# scratchBotV2.net
KiCad netlist of a schematic drawn in EAGLE
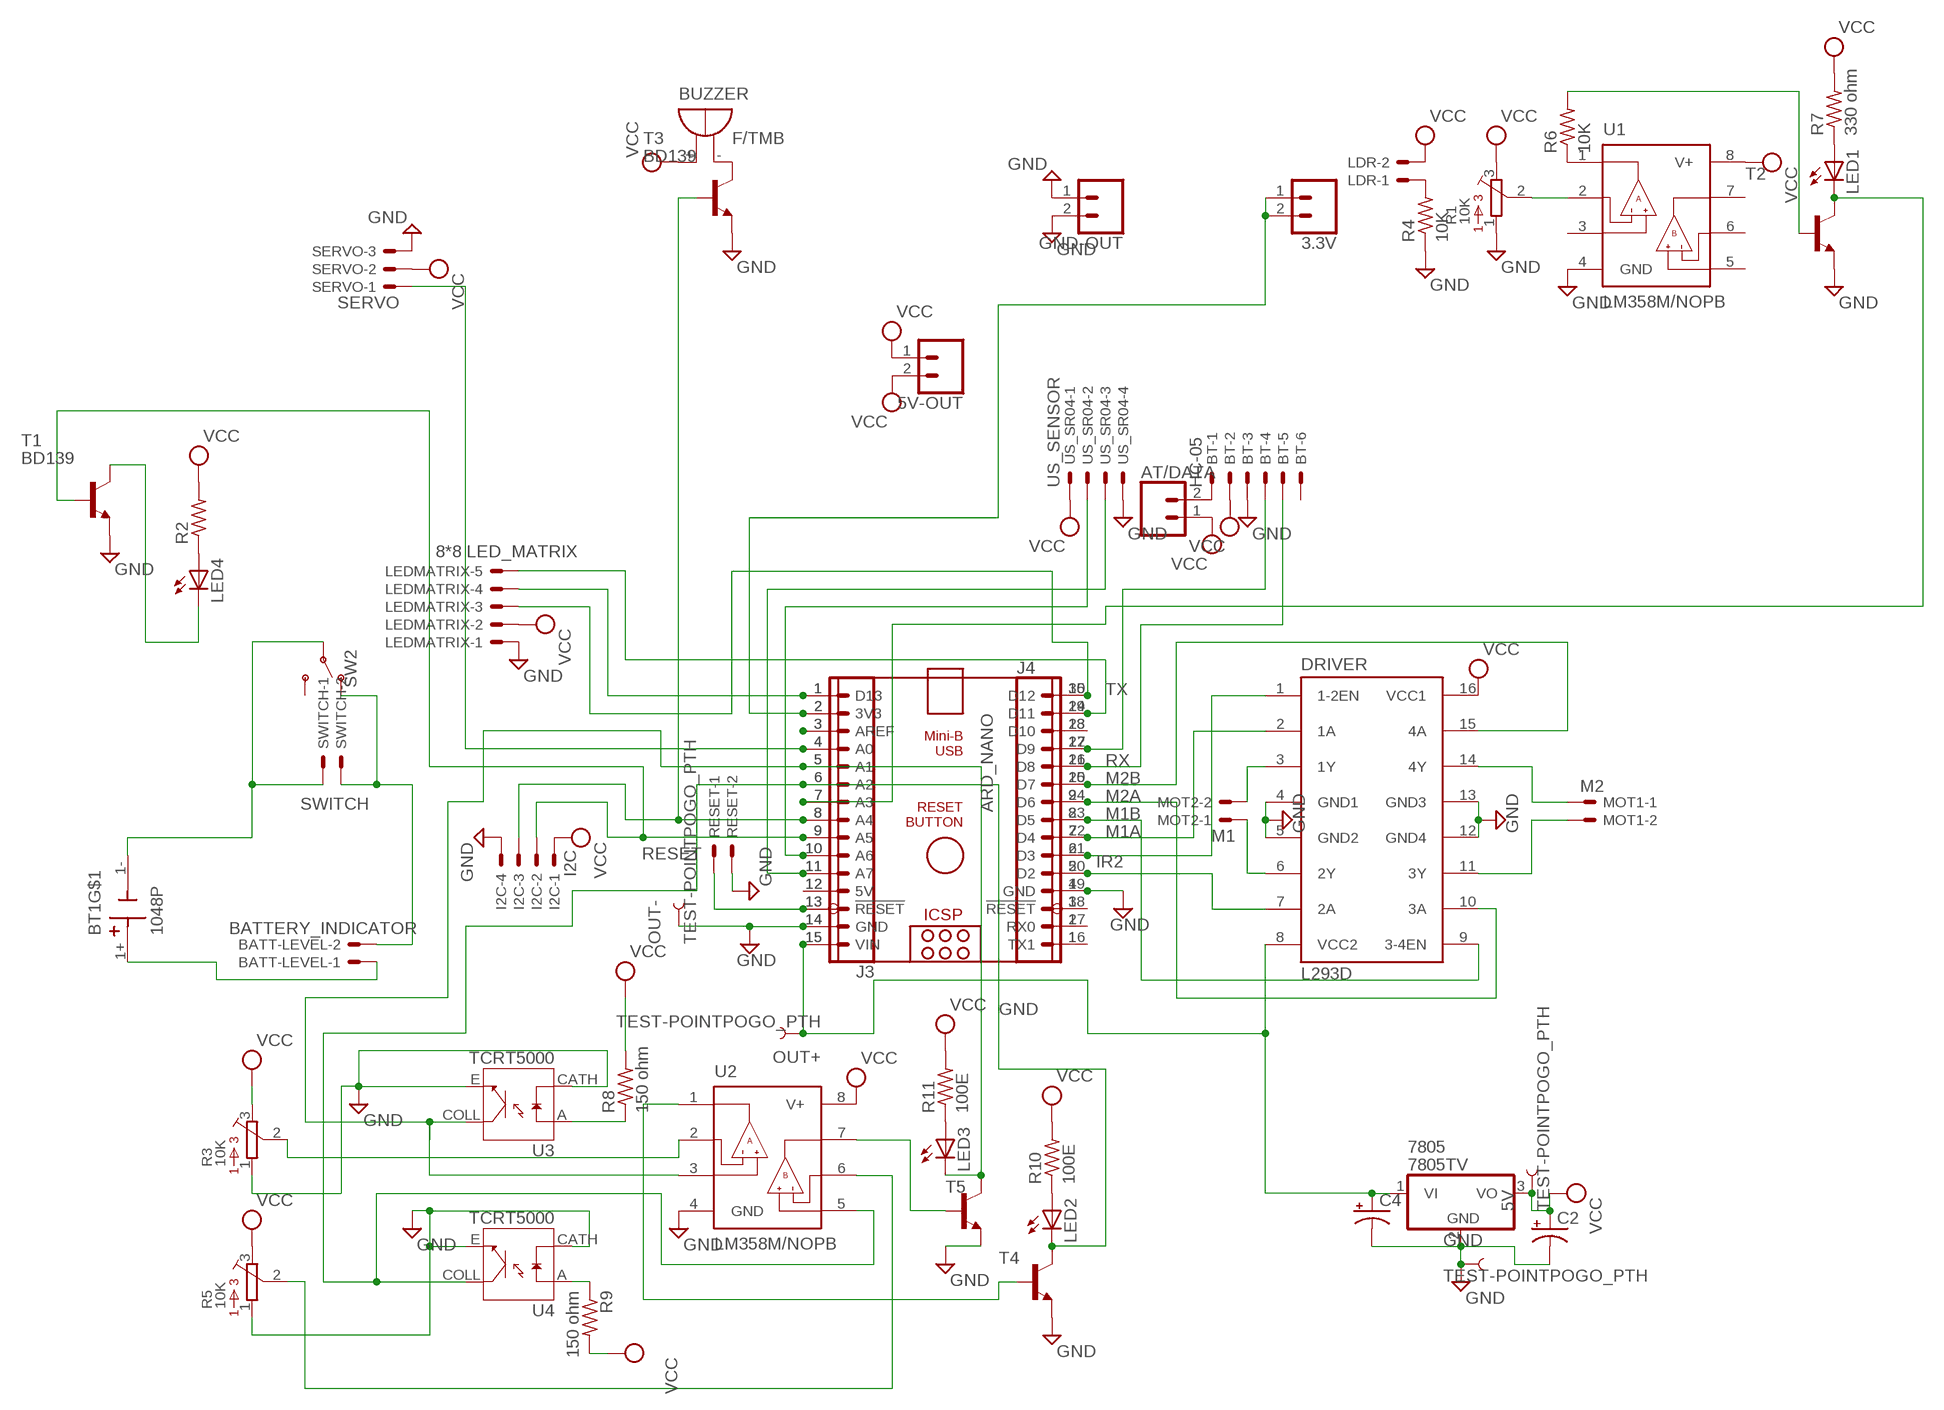
[diagram p0: schematic, sheet 1]

(export (version "E")
  (design (tool "Eeschema 10.0.6"))
  (components
    (comp (ref "3.3V")
      (value "CONN_02")
      (footprint "eagle-import:1X02")
      (libsource (lib "eagle-import") (part "CONN_02"))
    )
    (comp (ref "5V")
      (value "TEST-POINTPOGO_PTH")
      (footprint "eagle-import:1X01_NO_SILK")
      (libsource (lib "eagle-import") (part "TEST-POINTPOGO_PTH"))
    )
    (comp (ref "5V-OUT")
      (value "CONN_02")
      (footprint "eagle-import:1X02")
      (libsource (lib "eagle-import") (part "CONN_02"))
    )
    (comp (ref "7805")
      (value "7805TV")
      (footprint "eagle-import:TO220V")
      (libsource (lib "eagle-import") (part "78TV05"))
    )
    (comp (ref "ARD_NANO")
      (value "ARDUINO_NANO")
      (footprint "eagle-import:ARDUINO_NANO")
      (libsource (lib "eagle-import") (part "ARDUINO_NANO"))
    )
    (comp (ref "AT/DATA")
      (value "CONN_02")
      (footprint "eagle-import:1X02")
      (libsource (lib "eagle-import") (part "CONN_02"))
    )
    (comp (ref "BATT-LEVEL")
      (value "BATTERY_INDICATOR")
      (footprint "eagle-import:JST-XH-02-PACKAGE-LONG-PAD")
      (libsource (lib "eagle-import") (part "Rembrandt Electronics - JST XH Connectors v1-0 (1)_JST-XH-02-PIN-LONG-PAD"))
    )
    (comp (ref "BT")
      (value "HC-05")
      (footprint "eagle-import:JST-XH-06-PACKAGE-LONG-PAD")
      (libsource (lib "eagle-import") (part "JST-XH-06-PIN-LONG-PAD"))
    )
    (comp (ref "BT1")
      (value "1048P")
      (footprint "eagle-import:BAT_1048P")
      (fields (field (name "MF") "Keystone Electronics"))
      (libsource (lib "eagle-import") (part "1048P"))
    )
    (comp (ref "BUZZER")
      (value "F/TMB")
      (footprint "eagle-import:F_TMB")
      (libsource (lib "eagle-import") (part "F/TMB"))
    )
    (comp (ref "C2")
      (value "CPOL-USE2.5-5")
      (footprint "eagle-import:E2,5-5")
      (libsource (lib "eagle-import") (part "CPOL-USE2.5-5"))
    )
    (comp (ref "C4")
      (value "CPOL-USE2.5-5")
      (footprint "eagle-import:E2,5-5")
      (libsource (lib "eagle-import") (part "CPOL-USE2.5-5"))
    )
    (comp (ref "DRIVER")
      (value "L293D")
      (footprint "eagle-import:DIL16")
      (libsource (lib "eagle-import") (part "L293D"))
    )
    (comp (ref "GND")
      (value "TEST-POINTPOGO_PTH")
      (footprint "eagle-import:1X01_NO_SILK")
      (libsource (lib "eagle-import") (part "TEST-POINTPOGO_PTH"))
    )
    (comp (ref "GND-OUT")
      (value "CONN_02")
      (footprint "eagle-import:1X02")
      (libsource (lib "eagle-import") (part "CONN_02"))
    )
    (comp (ref "I2C")
      (value "I2C")
      (footprint "eagle-import:JST-XH-04-PACKAGE-LONG-PAD")
      (libsource (lib "eagle-import") (part "JST-XH-04-PIN-LONG-PAD"))
    )
    (comp (ref "J3")
      (value "CONN_15")
      (footprint "eagle-import:1X15")
      (libsource (lib "eagle-import") (part "CONN_15"))
    )
    (comp (ref "J4")
      (value "CONN_15")
      (footprint "eagle-import:1X15")
      (libsource (lib "eagle-import") (part "CONN_15"))
    )
    (comp (ref "LDR")
      (value "JST-XH-02-PIN-LONG-PAD")
      (footprint "eagle-import:JST-XH-02-PACKAGE-LONG-PAD")
      (libsource (lib "eagle-import") (part "JST-XH-02-PIN-LONG-PAD"))
    )
    (comp (ref "LED1")
      (value "LEDCHIPLED_1206")
      (footprint "eagle-import:CHIPLED_1206")
      (libsource (lib "eagle-import") (part "LEDCHIPLED_1206"))
    )
    (comp (ref "LED2")
      (value "LEDCHIPLED_1206")
      (footprint "eagle-import:CHIPLED_1206")
      (libsource (lib "eagle-import") (part "LEDCHIPLED_1206"))
    )
    (comp (ref "LED3")
      (value "LEDCHIPLED_1206")
      (footprint "eagle-import:CHIPLED_1206")
      (libsource (lib "eagle-import") (part "LEDCHIPLED_1206"))
    )
    (comp (ref "LED4")
      (value "LEDCHIPLED_1206")
      (footprint "eagle-import:CHIPLED_1206")
      (libsource (lib "eagle-import") (part "LEDCHIPLED_1206"))
    )
    (comp (ref "LEDMATRIX")
      (value "8*8 LED_MATRIX")
      (footprint "eagle-import:JST-XH-05-PACKAGE-LONG-PAD")
      (libsource (lib "eagle-import") (part "JST-XH-05-PIN-LONG-PAD"))
    )
    (comp (ref "MOT1")
      (value "M2")
      (footprint "eagle-import:JST-XH-02-PACKAGE-LONG-PAD")
      (libsource (lib "eagle-import") (part "Rembrandt Electronics - JST XH Connectors v1-0 (1)_JST-XH-02-PIN-LONG-PAD"))
    )
    (comp (ref "MOT2")
      (value "M1")
      (footprint "eagle-import:JST-XH-02-PACKAGE-LONG-PAD")
      (libsource (lib "eagle-import") (part "Rembrandt Electronics - JST XH Connectors v1-0 (1)_JST-XH-02-PIN-LONG-PAD"))
    )
    (comp (ref "OUT+")
      (value "TEST-POINTPOGO_PTH")
      (footprint "eagle-import:1X01_NO_SILK")
      (libsource (lib "eagle-import") (part "TEST-POINTPOGO_PTH"))
    )
    (comp (ref "OUT-")
      (value "TEST-POINTPOGO_PTH")
      (footprint "eagle-import:1X01_NO_SILK")
      (libsource (lib "eagle-import") (part "TEST-POINTPOGO_PTH"))
    )
    (comp (ref "R1")
      (value "10K")
      (footprint "eagle-import:3362H")
      (libsource (lib "eagle-import") (part "3362H"))
    )
    (comp (ref "R2")
      (value "R-US_0204/7")
      (footprint "eagle-import:0204_7")
      (libsource (lib "eagle-import") (part "R-US_0204/7"))
    )
    (comp (ref "R3")
      (value "10K")
      (footprint "eagle-import:3362H")
      (libsource (lib "eagle-import") (part "3362H"))
    )
    (comp (ref "R4")
      (value "10K")
      (footprint "eagle-import:M1206")
      (libsource (lib "eagle-import") (part "R-US_M1206"))
    )
    (comp (ref "R5")
      (value "10K")
      (footprint "eagle-import:3362H")
      (libsource (lib "eagle-import") (part "3362H"))
    )
    (comp (ref "R6")
      (value "10K")
      (footprint "eagle-import:M1206")
      (libsource (lib "eagle-import") (part "R-US_M1206"))
    )
    (comp (ref "R7")
      (value "330 ohm")
      (footprint "eagle-import:M1206")
      (libsource (lib "eagle-import") (part "R-US_M1206"))
    )
    (comp (ref "R8")
      (value "150 ohm")
      (footprint "eagle-import:M1206")
      (libsource (lib "eagle-import") (part "R-US_M1206"))
    )
    (comp (ref "R9")
      (value "150 ohm")
      (footprint "eagle-import:M1206")
      (libsource (lib "eagle-import") (part "R-US_M1206"))
    )
    (comp (ref "R10")
      (value "100E")
      (footprint "eagle-import:M1206")
      (libsource (lib "eagle-import") (part "R-US_M1206"))
    )
    (comp (ref "R11")
      (value "100E")
      (footprint "eagle-import:M1206")
      (libsource (lib "eagle-import") (part "R-US_M1206"))
    )
    (comp (ref "RESET")
      (value "RESET")
      (footprint "eagle-import:JST-XH-02-PACKAGE-LONG-PAD")
      (libsource (lib "eagle-import") (part "Rembrandt Electronics - JST XH Connectors v1-0 (1)_JST-XH-02-PIN-LONG-PAD"))
    )
    (comp (ref "SERVO")
      (value "SERVO")
      (footprint "eagle-import:JST-XH-03-PACKAGE-LONG-PAD")
      (libsource (lib "eagle-import") (part "JST-XH-03-PIN-LONG-PAD"))
    )
    (comp (ref "SW2")
      (value "SWITCH-SPDT-PTH-11.6X4.0MM")
      (footprint "eagle-import:SWITCH_SPDT_PTH_11.6X4.0MM")
      (libsource (lib "eagle-import") (part "SWITCH-SPDT-PTH-11.6X4.0MM"))
    )
    (comp (ref "SWITCH")
      (value "SWITCH")
      (footprint "eagle-import:JST-XH-02-PACKAGE-LONG-PAD")
      (libsource (lib "eagle-import") (part "Rembrandt Electronics - JST XH Connectors v1-0 (1)_JST-XH-02-PIN-LONG-PAD"))
    )
    (comp (ref "T1")
      (value "BD139")
      (footprint "eagle-import:TO126")
      (libsource (lib "eagle-import") (part "BD139"))
    )
    (comp (ref "T2")
      (value "-NPN-SOT23-EBC")
      (footprint "eagle-import:SOT23-EBC")
      (libsource (lib "eagle-import") (part "-NPN-SOT23-EBC"))
    )
    (comp (ref "T3")
      (value "BD139")
      (footprint "eagle-import:TO126")
      (libsource (lib "eagle-import") (part "BD139"))
    )
    (comp (ref "T4")
      (value "-NPN-SOT23-EBC")
      (footprint "eagle-import:SOT23-EBC")
      (libsource (lib "eagle-import") (part "-NPN-SOT23-EBC"))
    )
    (comp (ref "T5")
      (value "-NPN-SOT23-EBC")
      (footprint "eagle-import:SOT23-EBC")
      (libsource (lib "eagle-import") (part "-NPN-SOT23-EBC"))
    )
    (comp (ref "U1")
      (value "LM358M/NOPB")
      (footprint "eagle-import:SOIC127P599X175-8N")
      (fields (field (name "MF") "Texas Instruments"))
      (libsource (lib "eagle-import") (part "LM358M/NOPB"))
    )
    (comp (ref "U2")
      (value "LM358M/NOPB")
      (footprint "eagle-import:SOIC127P599X175-8N")
      (fields (field (name "MF") "Texas Instruments"))
      (libsource (lib "eagle-import") (part "LM358M/NOPB"))
    )
    (comp (ref "U3")
      (value "TCRT5000")
      (footprint "eagle-import:OPTO_TCRT5000")
      (fields (field (name "MF") "Vishay"))
      (libsource (lib "eagle-import") (part "TCRT5000"))
    )
    (comp (ref "U4")
      (value "TCRT5000")
      (footprint "eagle-import:OPTO_TCRT5000")
      (fields (field (name "MF") "Vishay"))
      (libsource (lib "eagle-import") (part "TCRT5000"))
    )
    (comp (ref "US_SR04")
      (value "US_SENSOR")
      (footprint "eagle-import:JST-XH-04-PACKAGE-LONG-PAD")
      (libsource (lib "eagle-import") (part "JST-XH-04-PIN-LONG-PAD"))
    )
  )
  (nets
    (net (code "1") (name "/IR2") (class "Default")
      (node (ref "ARD_NANO") (pin "21") (pinfunction "D3_21") (pintype "bidirectional"))
      (node (ref "DRIVER") (pin "1") (pinfunction "1-2EN_1") (pintype "input"))
      (node (ref "J4") (pin "6") (pinfunction "6_6") (pintype "passive"))
    )
    (net (code "2") (name "/M1A") (class "Default")
      (node (ref "ARD_NANO") (pin "22") (pinfunction "D4_22") (pintype "bidirectional"))
      (node (ref "DRIVER") (pin "2") (pinfunction "1A_2") (pintype "input"))
      (node (ref "J4") (pin "7") (pinfunction "7_7") (pintype "passive"))
    )
    (net (code "3") (name "/M1B") (class "Default")
      (node (ref "ARD_NANO") (pin "23") (pinfunction "D5_23") (pintype "bidirectional"))
      (node (ref "DRIVER") (pin "9") (pinfunction "3-4EN_9") (pintype "input"))
      (node (ref "J4") (pin "8") (pinfunction "8_8") (pintype "passive"))
    )
    (net (code "4") (name "/M2A") (class "Default")
      (node (ref "ARD_NANO") (pin "24") (pinfunction "D6_24") (pintype "bidirectional"))
      (node (ref "DRIVER") (pin "10") (pinfunction "3A_10") (pintype "input"))
      (node (ref "J4") (pin "9") (pinfunction "9_9") (pintype "passive"))
    )
    (net (code "5") (name "/M2B") (class "Default")
      (node (ref "ARD_NANO") (pin "25") (pinfunction "D7_25") (pintype "bidirectional"))
      (node (ref "DRIVER") (pin "15") (pinfunction "4A_15") (pintype "input"))
      (node (ref "J4") (pin "10") (pinfunction "10_10") (pintype "passive"))
    )
    (net (code "6") (name "/RX") (class "Default")
      (node (ref "ARD_NANO") (pin "26") (pinfunction "D8_26") (pintype "bidirectional"))
      (node (ref "BT") (pin "5") (pinfunction "S_5") (pintype "passive"))
      (node (ref "J4") (pin "11") (pinfunction "11_11") (pintype "passive"))
    )
    (net (code "7") (name "/TX") (class "Default")
      (node (ref "ARD_NANO") (pin "30") (pinfunction "D12_30") (pintype "bidirectional"))
      (node (ref "J4") (pin "15") (pinfunction "15_15") (pintype "passive"))
      (node (ref "LEDMATRIX") (pin "3") (pinfunction "S_3") (pintype "passive"))
    )
    (net (code "8") (name "GND") (class "Default")
      (node (ref "7805") (pin "2") (pinfunction "GND_2") (pintype "passive"))
      (node (ref "ARD_NANO") (pin "14") (pinfunction "GND_14") (pintype "power_in"))
      (node (ref "ARD_NANO") (pin "19") (pinfunction "GND_19") (pintype "power_in"))
      (node (ref "BT") (pin "3") (pinfunction "S_3") (pintype "passive"))
      (node (ref "C2") (pin "-") (pinfunction "-_-") (pintype "passive"))
      (node (ref "C4") (pin "-") (pinfunction "-_-") (pintype "passive"))
      (node (ref "DRIVER") (pin "12") (pinfunction "GND4_12") (pintype "power_in"))
      (node (ref "DRIVER") (pin "13") (pinfunction "GND3_13") (pintype "power_in"))
      (node (ref "DRIVER") (pin "4") (pinfunction "GND1_4") (pintype "power_in"))
      (node (ref "DRIVER") (pin "5") (pinfunction "GND2_5") (pintype "power_in"))
      (node (ref "GND") (pin "1") (pinfunction "1_1") (pintype "bidirectional"))
      (node (ref "GND-OUT") (pin "1") (pinfunction "1_1") (pintype "passive"))
      (node (ref "GND-OUT") (pin "2") (pinfunction "2_2") (pintype "passive"))
      (node (ref "I2C") (pin "4") (pinfunction "S_4") (pintype "passive"))
      (node (ref "J3") (pin "14") (pinfunction "14_14") (pintype "passive"))
      (node (ref "J4") (pin "4") (pinfunction "4_4") (pintype "passive"))
      (node (ref "LEDMATRIX") (pin "1") (pinfunction "S_1") (pintype "passive"))
      (node (ref "OUT-") (pin "1") (pinfunction "1_1") (pintype "bidirectional"))
      (node (ref "R1") (pin "1") (pinfunction "1_1") (pintype "passive"))
      (node (ref "R3") (pin "1") (pinfunction "1_1") (pintype "passive"))
      (node (ref "R4") (pin "1") (pinfunction "1_1") (pintype "passive"))
      (node (ref "R5") (pin "1") (pinfunction "1_1") (pintype "passive"))
      (node (ref "RESET") (pin "2") (pinfunction "S_2") (pintype "passive"))
      (node (ref "SERVO") (pin "3") (pinfunction "S_3") (pintype "passive"))
      (node (ref "T1") (pin "1") (pinfunction "E_1") (pintype "passive"))
      (node (ref "T2") (pin "E") (pinfunction "E_E") (pintype "passive"))
      (node (ref "T3") (pin "1") (pinfunction "E_1") (pintype "passive"))
      (node (ref "T4") (pin "E") (pinfunction "E_E") (pintype "passive"))
      (node (ref "T5") (pin "E") (pinfunction "E_E") (pintype "passive"))
      (node (ref "U1") (pin "4") (pinfunction "GND_4") (pintype "power_in"))
      (node (ref "U2") (pin "4") (pinfunction "GND_4") (pintype "power_in"))
      (node (ref "U3") (pin "CATH") (pinfunction "CATH_CATH") (pintype "passive"))
      (node (ref "U3") (pin "E") (pinfunction "E_E") (pintype "passive"))
      (node (ref "U4") (pin "CATH") (pinfunction "CATH_CATH") (pintype "passive"))
      (node (ref "U4") (pin "E") (pinfunction "E_E") (pintype "passive"))
      (node (ref "US_SR04") (pin "4") (pinfunction "S_4") (pintype "passive"))
    )
    (net (code "9") (name "Net-(7805-VI)") (class "Default")
      (node (ref "7805") (pin "1") (pinfunction "VI_1") (pintype "input"))
      (node (ref "ARD_NANO") (pin "15") (pinfunction "VIN_15") (pintype "power_in"))
      (node (ref "C4") (pin "+") (pinfunction "+_+") (pintype "passive"))
      (node (ref "DRIVER") (pin "8") (pinfunction "VCC2_8") (pintype "power_in"))
      (node (ref "J3") (pin "15") (pinfunction "15_15") (pintype "passive"))
      (node (ref "OUT+") (pin "1") (pinfunction "1_1") (pintype "bidirectional"))
    )
    (net (code "10") (name "Net-(ARD_NANO-3V3)") (class "Default")
      (node (ref "3.3V") (pin "1") (pinfunction "1_1") (pintype "passive"))
      (node (ref "3.3V") (pin "2") (pinfunction "2_2") (pintype "passive"))
      (node (ref "ARD_NANO") (pin "2") (pinfunction "3V3_2") (pintype "output"))
      (node (ref "J3") (pin "2") (pinfunction "2_2") (pintype "passive"))
    )
    (net (code "11") (name "Net-(ARD_NANO-5V)") (class "Default")
      (node (ref "ARD_NANO") (pin "12") (pinfunction "5V_12") (pintype "power_in"))
      (node (ref "J3") (pin "12") (pinfunction "12_12") (pintype "passive"))
    )
    (net (code "12") (name "Net-(ARD_NANO-A0)") (class "Default")
      (node (ref "ARD_NANO") (pin "4") (pinfunction "A0_4") (pintype "bidirectional"))
      (node (ref "J3") (pin "4") (pinfunction "4_4") (pintype "passive"))
      (node (ref "SERVO") (pin "1") (pinfunction "S_1") (pintype "passive"))
    )
    (net (code "13") (name "Net-(ARD_NANO-A1)") (class "Default")
      (node (ref "ARD_NANO") (pin "5") (pinfunction "A1_5") (pintype "bidirectional"))
      (node (ref "J3") (pin "5") (pinfunction "5_5") (pintype "passive"))
      (node (ref "LED3") (pin "C") (pinfunction "C_C") (pintype "passive"))
      (node (ref "T5") (pin "C") (pinfunction "C_C") (pintype "passive"))
      (node (ref "U2") (pin "3") (pinfunction "+INA_3") (pintype "input"))
      (node (ref "U3") (pin "COLL") (pinfunction "COLL_COLL") (pintype "passive"))
    )
    (net (code "14") (name "Net-(ARD_NANO-A2)") (class "Default")
      (node (ref "ARD_NANO") (pin "6") (pinfunction "A2_6") (pintype "bidirectional"))
      (node (ref "J3") (pin "6") (pinfunction "6_6") (pintype "passive"))
      (node (ref "LED2") (pin "C") (pinfunction "C_C") (pintype "passive"))
      (node (ref "T4") (pin "C") (pinfunction "C_C") (pintype "passive"))
      (node (ref "U2") (pin "5") (pinfunction "+INB_5") (pintype "input"))
      (node (ref "U4") (pin "COLL") (pinfunction "COLL_COLL") (pintype "passive"))
    )
    (net (code "15") (name "Net-(ARD_NANO-A3)") (class "Default")
      (node (ref "ARD_NANO") (pin "7") (pinfunction "A3_7") (pintype "bidirectional"))
      (node (ref "J3") (pin "7") (pinfunction "7_7") (pintype "passive"))
      (node (ref "LED1") (pin "C") (pinfunction "C_C") (pintype "passive"))
      (node (ref "T2") (pin "C") (pinfunction "C_C") (pintype "passive"))
    )
    (net (code "16") (name "Net-(ARD_NANO-A4)") (class "Default")
      (node (ref "ARD_NANO") (pin "8") (pinfunction "A4_8") (pintype "bidirectional"))
      (node (ref "I2C") (pin "3") (pinfunction "S_3") (pintype "passive"))
      (node (ref "J3") (pin "8") (pinfunction "8_8") (pintype "passive"))
      (node (ref "T3") (pin "3") (pinfunction "B_3") (pintype "passive"))
    )
    (net (code "17") (name "Net-(ARD_NANO-A5)") (class "Default")
      (node (ref "ARD_NANO") (pin "9") (pinfunction "A5_9") (pintype "bidirectional"))
      (node (ref "I2C") (pin "2") (pinfunction "S_2") (pintype "passive"))
      (node (ref "J3") (pin "9") (pinfunction "9_9") (pintype "passive"))
      (node (ref "T1") (pin "3") (pinfunction "B_3") (pintype "passive"))
    )
    (net (code "18") (name "Net-(ARD_NANO-A6)") (class "Default")
      (node (ref "ARD_NANO") (pin "10") (pinfunction "A6_10") (pintype "bidirectional"))
      (node (ref "J3") (pin "10") (pinfunction "10_10") (pintype "passive"))
      (node (ref "US_SR04") (pin "2") (pinfunction "S_2") (pintype "passive"))
    )
    (net (code "19") (name "Net-(ARD_NANO-A7)") (class "Default")
      (node (ref "ARD_NANO") (pin "11") (pinfunction "A7_11") (pintype "bidirectional"))
      (node (ref "J3") (pin "11") (pinfunction "11_11") (pintype "passive"))
      (node (ref "US_SR04") (pin "3") (pinfunction "S_3") (pintype "passive"))
    )
    (net (code "20") (name "Net-(ARD_NANO-AREF)") (class "Default")
      (node (ref "ARD_NANO") (pin "3") (pinfunction "AREF_3") (pintype "input"))
      (node (ref "J3") (pin "3") (pinfunction "3_3") (pintype "passive"))
    )
    (net (code "21") (name "Net-(ARD_NANO-D2)") (class "Default")
      (node (ref "ARD_NANO") (pin "20") (pinfunction "D2_20") (pintype "bidirectional"))
      (node (ref "DRIVER") (pin "7") (pinfunction "2A_7") (pintype "input"))
      (node (ref "J4") (pin "5") (pinfunction "5_5") (pintype "passive"))
    )
    (net (code "22") (name "Net-(ARD_NANO-D9)") (class "Default")
      (node (ref "ARD_NANO") (pin "27") (pinfunction "D9_27") (pintype "bidirectional"))
      (node (ref "BT") (pin "4") (pinfunction "S_4") (pintype "passive"))
      (node (ref "J4") (pin "12") (pinfunction "12_12") (pintype "passive"))
    )
    (net (code "23") (name "Net-(ARD_NANO-D10)") (class "Default")
      (node (ref "ARD_NANO") (pin "28") (pinfunction "D10_28") (pintype "bidirectional"))
      (node (ref "J4") (pin "13") (pinfunction "13_13") (pintype "passive"))
    )
    (net (code "24") (name "Net-(ARD_NANO-D11)") (class "Default")
      (node (ref "ARD_NANO") (pin "29") (pinfunction "D11_29") (pintype "bidirectional"))
      (node (ref "J4") (pin "14") (pinfunction "14_14") (pintype "passive"))
      (node (ref "LEDMATRIX") (pin "5") (pinfunction "S_5") (pintype "passive"))
    )
    (net (code "25") (name "Net-(ARD_NANO-D13)") (class "Default")
      (node (ref "ARD_NANO") (pin "1") (pinfunction "D13_1") (pintype "bidirectional"))
      (node (ref "J3") (pin "1") (pinfunction "1_1") (pintype "passive"))
      (node (ref "LEDMATRIX") (pin "4") (pinfunction "S_4") (pintype "passive"))
    )
    (net (code "26") (name "Net-(ARD_NANO-RX0)") (class "Default")
      (node (ref "ARD_NANO") (pin "17") (pinfunction "RX0_17") (pintype "bidirectional"))
      (node (ref "J4") (pin "2") (pinfunction "2_2") (pintype "passive"))
    )
    (net (code "27") (name "Net-(ARD_NANO-TX1)") (class "Default")
      (node (ref "ARD_NANO") (pin "16") (pinfunction "TX1_16") (pintype "bidirectional"))
      (node (ref "J4") (pin "1") (pinfunction "1_1") (pintype "passive"))
    )
    (net (code "28") (name "Net-(ARD_NANO-~{RESET}-Pad18)") (class "Default")
      (node (ref "ARD_NANO") (pin "18") (pinfunction "~{RESET}_18") (pintype "input"))
      (node (ref "J4") (pin "3") (pinfunction "3_3") (pintype "passive"))
    )
    (net (code "29") (name "Net-(BATT-LEVELA-S)") (class "Default")
      (node (ref "BATT-LEVEL") (pin "1") (pinfunction "S_1") (pintype "passive"))
      (node (ref "BT1") (pin "1+") (pinfunction "1+_1+") (pintype "passive"))
    )
    (net (code "30") (name "Net-(BATT-LEVELB-S)") (class "Default")
      (node (ref "BATT-LEVEL") (pin "2") (pinfunction "S_2") (pintype "passive"))
      (node (ref "SW2") (pin "1") (pinfunction "O_1") (pintype "passive"))
      (node (ref "SWITCH") (pin "2") (pinfunction "S_2") (pintype "passive"))
    )
    (net (code "31") (name "Net-(BTA-S)") (class "Default")
      (node (ref "AT/DATA") (pin "2") (pinfunction "2_2") (pintype "passive"))
      (node (ref "BT") (pin "1") (pinfunction "S_1") (pintype "passive"))
    )
    (net (code "32") (name "Net-(DRIVER-1Y)") (class "Default")
      (node (ref "DRIVER") (pin "3") (pinfunction "1Y_3") (pintype "output"))
      (node (ref "MOT2") (pin "2") (pinfunction "S_2") (pintype "passive"))
    )
    (net (code "33") (name "Net-(DRIVER-2Y)") (class "Default")
      (node (ref "DRIVER") (pin "6") (pinfunction "2Y_6") (pintype "output"))
      (node (ref "MOT2") (pin "1") (pinfunction "S_1") (pintype "passive"))
    )
    (net (code "34") (name "Net-(DRIVER-3Y)") (class "Default")
      (node (ref "DRIVER") (pin "11") (pinfunction "3Y_11") (pintype "output"))
      (node (ref "MOT1") (pin "2") (pinfunction "S_2") (pintype "passive"))
    )
    (net (code "35") (name "Net-(DRIVER-4Y)") (class "Default")
      (node (ref "DRIVER") (pin "14") (pinfunction "4Y_14") (pintype "output"))
      (node (ref "MOT1") (pin "1") (pinfunction "S_1") (pintype "passive"))
    )
    (net (code "36") (name "Net-(LDRA-S)") (class "Default")
      (node (ref "LDR") (pin "1") (pinfunction "S_1") (pintype "passive"))
      (node (ref "R4") (pin "2") (pinfunction "2_2") (pintype "passive"))
    )
    (net (code "37") (name "Net-(LED1-PadA)") (class "Default")
      (node (ref "LED1") (pin "A") (pinfunction "A_A") (pintype "passive"))
      (node (ref "R7") (pin "1") (pinfunction "1_1") (pintype "passive"))
    )
    (net (code "38") (name "Net-(LED2-PadA)") (class "Default")
      (node (ref "LED2") (pin "A") (pinfunction "A_A") (pintype "passive"))
      (node (ref "R10") (pin "1") (pinfunction "1_1") (pintype "passive"))
    )
    (net (code "39") (name "Net-(LED3-PadA)") (class "Default")
      (node (ref "LED3") (pin "A") (pinfunction "A_A") (pintype "passive"))
      (node (ref "R11") (pin "1") (pinfunction "1_1") (pintype "passive"))
    )
    (net (code "40") (name "Net-(LED4-PadA)") (class "Default")
      (node (ref "LED4") (pin "A") (pinfunction "A_A") (pintype "passive"))
      (node (ref "R2") (pin "1") (pinfunction "1_1") (pintype "passive"))
    )
    (net (code "41") (name "Net-(R6-Pad2)") (class "Default")
      (node (ref "R6") (pin "2") (pinfunction "2_2") (pintype "passive"))
      (node (ref "T2") (pin "B") (pinfunction "B_B") (pintype "passive"))
    )
    (net (code "42") (name "Net-(R8-Pad1)") (class "Default")
      (node (ref "R8") (pin "1") (pinfunction "1_1") (pintype "passive"))
      (node (ref "U3") (pin "A") (pinfunction "A_A") (pintype "passive"))
    )
    (net (code "43") (name "Net-(R9-Pad1)") (class "Default")
      (node (ref "R9") (pin "1") (pinfunction "1_1") (pintype "passive"))
      (node (ref "U4") (pin "A") (pinfunction "A_A") (pintype "passive"))
    )
    (net (code "44") (name "Net-(RESETA-S)") (class "Default")
      (node (ref "ARD_NANO") (pin "13") (pinfunction "~{RESET}_13") (pintype "input"))
      (node (ref "J3") (pin "13") (pinfunction "13_13") (pintype "passive"))
      (node (ref "RESET") (pin "1") (pinfunction "S_1") (pintype "passive"))
    )
    (net (code "45") (name "Net-(SW2-P)") (class "Default")
      (node (ref "BT1") (pin "1-") (pinfunction "1-_1-") (pintype "passive"))
      (node (ref "SW2") (pin "2") (pinfunction "P_2") (pintype "passive"))
      (node (ref "SWITCH") (pin "1") (pinfunction "S_1") (pintype "passive"))
    )
    (net (code "46") (name "Net-(T1-C)") (class "Default")
      (node (ref "LED4") (pin "C") (pinfunction "C_C") (pintype "passive"))
      (node (ref "T1") (pin "2") (pinfunction "C_2") (pintype "passive"))
    )
    (net (code "47") (name "Net-(T3-C)") (class "Default")
      (node (ref "BUZZER") (pin "-") (pinfunction "-_-") (pintype "passive"))
      (node (ref "T3") (pin "2") (pinfunction "C_2") (pintype "passive"))
    )
    (net (code "48") (name "Net-(U1--INA)") (class "Default")
      (node (ref "R1") (pin "2") (pinfunction "2_2") (pintype "passive"))
      (node (ref "U1") (pin "2") (pinfunction "-INA_2") (pintype "input"))
    )
    (net (code "49") (name "Net-(U1-OUTA)") (class "Default")
      (node (ref "R6") (pin "1") (pinfunction "1_1") (pintype "passive"))
      (node (ref "U1") (pin "1") (pinfunction "OUTA_1") (pintype "output"))
    )
    (net (code "50") (name "Net-(U2--INA)") (class "Default")
      (node (ref "R3") (pin "2") (pinfunction "2_2") (pintype "passive"))
      (node (ref "U2") (pin "2") (pinfunction "-INA_2") (pintype "input"))
    )
    (net (code "51") (name "Net-(U2--INB)") (class "Default")
      (node (ref "R5") (pin "2") (pinfunction "2_2") (pintype "passive"))
      (node (ref "U2") (pin "6") (pinfunction "-INB_6") (pintype "input"))
    )
    (net (code "52") (name "Net-(U2-OUTA)") (class "Default")
      (node (ref "T4") (pin "B") (pinfunction "B_B") (pintype "passive"))
      (node (ref "U2") (pin "1") (pinfunction "OUTA_1") (pintype "output"))
    )
    (net (code "53") (name "Net-(U2-OUTB)") (class "Default")
      (node (ref "T5") (pin "B") (pinfunction "B_B") (pintype "passive"))
      (node (ref "U2") (pin "7") (pinfunction "OUTB_7") (pintype "output"))
    )
    (net (code "54") (name "VCC") (class "Default")
      (node (ref "5V") (pin "1") (pinfunction "1_1") (pintype "bidirectional"))
      (node (ref "5V-OUT") (pin "1") (pinfunction "1_1") (pintype "passive"))
      (node (ref "5V-OUT") (pin "2") (pinfunction "2_2") (pintype "passive"))
      (node (ref "7805") (pin "3") (pinfunction "VO_3") (pintype "passive"))
      (node (ref "AT/DATA") (pin "1") (pinfunction "1_1") (pintype "passive"))
      (node (ref "BT") (pin "2") (pinfunction "S_2") (pintype "passive"))
      (node (ref "BUZZER") (pin "+") (pinfunction "+_+") (pintype "passive"))
      (node (ref "C2") (pin "+") (pinfunction "+_+") (pintype "passive"))
      (node (ref "DRIVER") (pin "16") (pinfunction "VCC1_16") (pintype "power_in"))
      (node (ref "I2C") (pin "1") (pinfunction "S_1") (pintype "passive"))
      (node (ref "LDR") (pin "2") (pinfunction "S_2") (pintype "passive"))
      (node (ref "LEDMATRIX") (pin "2") (pinfunction "S_2") (pintype "passive"))
      (node (ref "R1") (pin "3") (pinfunction "3_3") (pintype "passive"))
      (node (ref "R10") (pin "2") (pinfunction "2_2") (pintype "passive"))
      (node (ref "R11") (pin "2") (pinfunction "2_2") (pintype "passive"))
      (node (ref "R2") (pin "2") (pinfunction "2_2") (pintype "passive"))
      (node (ref "R3") (pin "3") (pinfunction "3_3") (pintype "passive"))
      (node (ref "R5") (pin "3") (pinfunction "3_3") (pintype "passive"))
      (node (ref "R7") (pin "2") (pinfunction "2_2") (pintype "passive"))
      (node (ref "R8") (pin "2") (pinfunction "2_2") (pintype "passive"))
      (node (ref "R9") (pin "2") (pinfunction "2_2") (pintype "passive"))
      (node (ref "SERVO") (pin "2") (pinfunction "S_2") (pintype "passive"))
      (node (ref "U1") (pin "8") (pinfunction "V+_8") (pintype "power_in"))
      (node (ref "U2") (pin "8") (pinfunction "V+_8") (pintype "power_in"))
      (node (ref "US_SR04") (pin "1") (pinfunction "S_1") (pintype "passive"))
    )
    (net (code "55") (name "unconnected-(BTF-S-Pad6)") (class "Default")
      (node (ref "BT") (pin "6") (pinfunction "S_6") (pintype "passive"))
    )
    (net (code "56") (name "unconnected-(SW2-S-Pad3)") (class "Default")
      (node (ref "SW2") (pin "3") (pinfunction "S_3") (pintype "passive"))
    )
    (net (code "57") (name "unconnected-(U1-+INA-Pad3)") (class "Default")
      (node (ref "U1") (pin "3") (pinfunction "+INA_3") (pintype "input"))
    )
    (net (code "58") (name "unconnected-(U1-+INB-Pad5)") (class "Default")
      (node (ref "U1") (pin "5") (pinfunction "+INB_5") (pintype "input"))
    )
    (net (code "59") (name "unconnected-(U1--INB-Pad6)") (class "Default")
      (node (ref "U1") (pin "6") (pinfunction "-INB_6") (pintype "input"))
    )
    (net (code "60") (name "unconnected-(U1-OUTB-Pad7)") (class "Default")
      (node (ref "U1") (pin "7") (pinfunction "OUTB_7") (pintype "output"))
    )
  )
)
